# top.net
KiCad netlist of a schematic drawn in Altium Designer
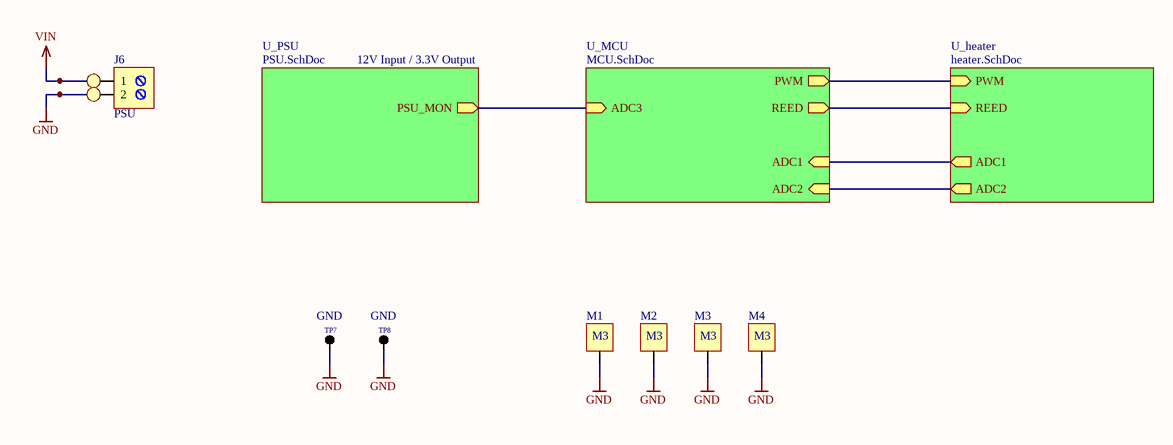
[diagram p0: top.SchDoc]

(export (version "E")
  (design (tool "Eeschema 10.0.6"))
  (components
    (comp (ref "J6")
      (value "PSU")
      (footprint "J_ARK2")
      (description "ARK Screw terminal, 2-Pin")
      (fields (field (name "PART NUMBER") "J_TB-5.0-P-2P") (field (name "MANUFACTURER") "DEGSON ELECTRONICS"))
      (libsource (lib "Library") (part "J_ARK2"))
    )
    (comp (ref "M1")
      (value "M3 Hole")
      (footprint "M3 Hole")
      (description "Inner diamater 3.25 mm Outer diamerer 6 mm")
      (libsource (lib "Lib - Mechanical") (part "M3 Hole"))
    )
    (comp (ref "M2")
      (value "M3 Hole")
      (footprint "M3 Hole")
      (description "Inner diamater 3.25 mm Outer diamerer 6 mm")
      (libsource (lib "Lib - Mechanical") (part "M3 Hole"))
    )
    (comp (ref "M3")
      (value "M3 Hole")
      (footprint "M3 Hole")
      (description "Inner diamater 3.25 mm Outer diamerer 6 mm")
      (libsource (lib "Lib - Mechanical") (part "M3 Hole"))
    )
    (comp (ref "M4")
      (value "M3 Hole")
      (footprint "M3 Hole")
      (description "Inner diamater 3.25 mm Outer diamerer 6 mm")
      (libsource (lib "Lib - Mechanical") (part "M3 Hole"))
    )
    (comp (ref "PAD1")
      (value "PAD")
      (footprint "PAD_08mm")
      (description "PCB Pad")
      (fields (field (name "PART NUMBER") "J_PAD"))
      (libsource (lib "Library") (part "PAD"))
    )
    (comp (ref "PAD2")
      (value "PAD")
      (footprint "PAD_08mm")
      (description "PCB Pad")
      (fields (field (name "PART NUMBER") "J_PAD"))
      (libsource (lib "Library") (part "PAD"))
    )
    (comp (ref "TP7")
      (value "GND")
      (footprint "TP_PAD")
      (description "Testpoint")
      (fields (field (name "PART NUMBER") "TP_PAD"))
      (libsource (lib "Library") (part "TP_TESTPOINT"))
    )
    (comp (ref "TP8")
      (value "GND")
      (footprint "TP_PAD")
      (description "Testpoint")
      (fields (field (name "PART NUMBER") "TP_PAD"))
      (libsource (lib "Library") (part "TP_TESTPOINT"))
    )
  )
  (nets
    (net (code "6") (name "GND") (class "Default")
      (node (ref "J6") (pin "2") (pinfunction "2_2") (pintype "passive"))
      (node (ref "M1") (pin "1") (pintype "passive"))
      (node (ref "M2") (pin "1") (pintype "passive"))
      (node (ref "M3") (pin "1") (pintype "passive"))
      (node (ref "M4") (pin "1") (pintype "passive"))
      (node (ref "PAD2") (pin "1") (pintype "passive"))
      (node (ref "TP7") (pin "1") (pinfunction "TP_1") (pintype "passive"))
      (node (ref "TP8") (pin "1") (pinfunction "TP_1") (pintype "passive"))
    )
    (net (code "7") (name "VIN") (class "Default")
      (node (ref "J6") (pin "1") (pinfunction "1_1") (pintype "passive"))
      (node (ref "PAD1") (pin "1") (pintype "passive"))
    )
  )
)
